# es_shield.net
KiCad netlist of a schematic drawn in EAGLE
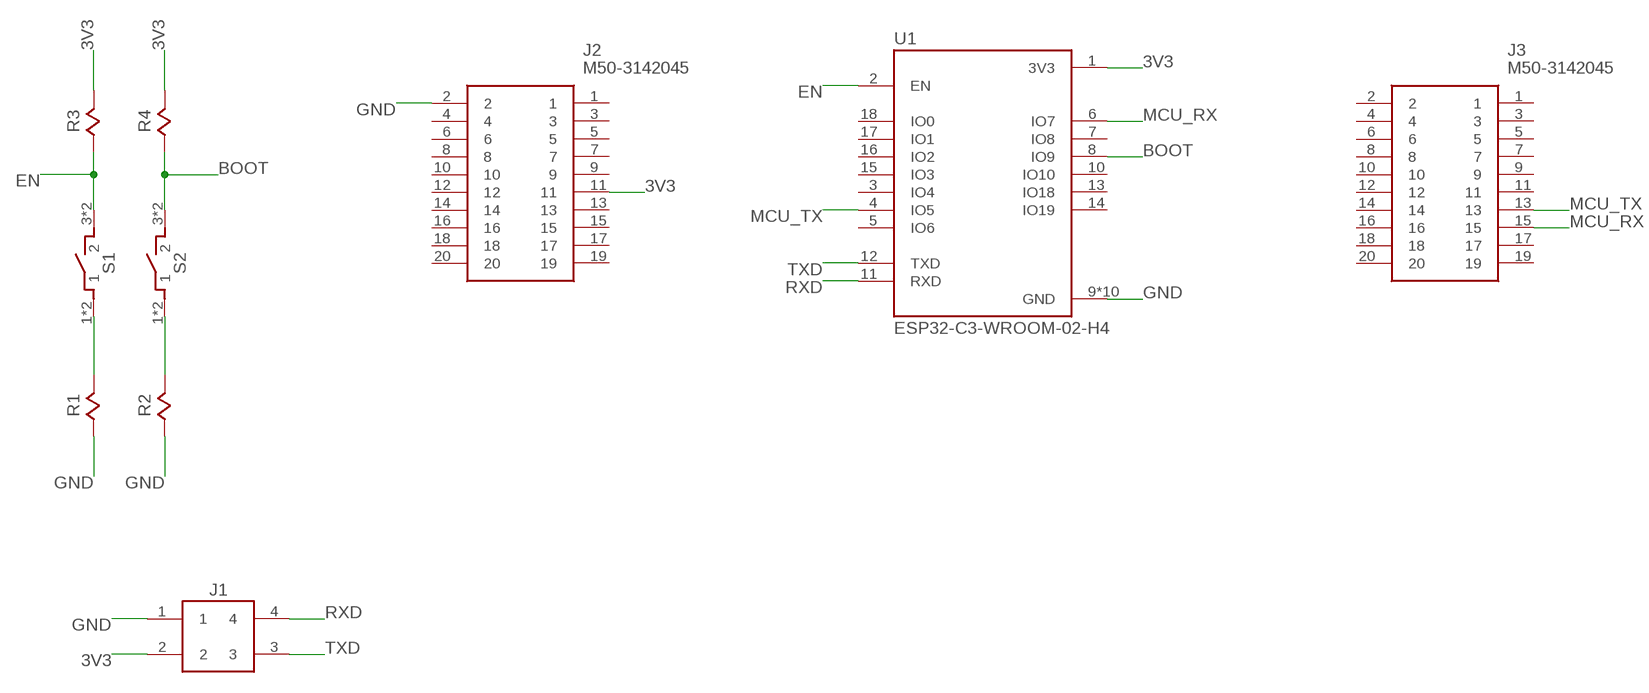
[diagram p0: schematic, sheet 1]

(export (version "E")
  (design (tool "Eeschema 10.0.6"))
  (components
    (comp (ref "J1")
      (value "MALE_HEADER_4X1")
      (footprint "eagle-import:4X1_HEADER")
      (libsource (lib "eagle-import") (part "MALE_HEADER_4X1"))
    )
    (comp (ref "J2")
      (value "M50-3142045")
      (footprint "eagle-import:M503142045")
      (fields (field (name "MOUSER_PART_NUMBER") "855-M50-3142045"))
      (libsource (lib "eagle-import") (part "M50-3142045"))
    )
    (comp (ref "J3")
      (value "M50-3142045")
      (footprint "eagle-import:M503142045")
      (fields (field (name "MOUSER_PART_NUMBER") "855-M50-3142045"))
      (libsource (lib "eagle-import") (part "M50-3142045"))
    )
    (comp (ref "R1")
      (value "RESISTOR")
      (footprint "eagle-import:0805")
      (libsource (lib "eagle-import") (part "RESISTOR"))
    )
    (comp (ref "R2")
      (value "RESISTOR")
      (footprint "eagle-import:0805")
      (libsource (lib "eagle-import") (part "RESISTOR"))
    )
    (comp (ref "R3")
      (value "RESISTOR")
      (footprint "eagle-import:0805")
      (libsource (lib "eagle-import") (part "RESISTOR"))
    )
    (comp (ref "R4")
      (value "RESISTOR")
      (footprint "eagle-import:0805")
      (libsource (lib "eagle-import") (part "RESISTOR"))
    )
    (comp (ref "S1")
      (value "TACTILE-SWITCH")
      (footprint "eagle-import:TACTILE-SWITCH")
      (libsource (lib "eagle-import") (part "TACTILE-SWITCH"))
    )
    (comp (ref "S2")
      (value "TACTILE-SWITCH")
      (footprint "eagle-import:TACTILE-SWITCH")
      (libsource (lib "eagle-import") (part "TACTILE-SWITCH"))
    )
    (comp (ref "U1")
      (value "ESP32-C3-WROOM-02-H4")
      (footprint "eagle-import:MODULE_ESP32-C3-WROOM-02-H4")
      (fields (field (name "MANUFACTURER") "Espressif"))
      (libsource (lib "eagle-import") (part "ESP32-C3-WROOM-02-H4"))
    )
  )
  (nets
    (net (code "1") (name "/3V3") (class "Default")
      (node (ref "J1") (pin "2") (pinfunction "2_2") (pintype "bidirectional"))
      (node (ref "J2") (pin "11") (pinfunction "11_11") (pintype "bidirectional"))
      (node (ref "R3") (pin "2") (pinfunction "2_2") (pintype "bidirectional"))
      (node (ref "R4") (pin "2") (pinfunction "2_2") (pintype "bidirectional"))
      (node (ref "U1") (pin "1") (pinfunction "3V3_1") (pintype "power_in"))
    )
    (net (code "2") (name "/BOOT") (class "Default")
      (node (ref "R4") (pin "1") (pinfunction "1_1") (pintype "bidirectional"))
      (node (ref "S2") (pin "3") (pinfunction "2_3") (pintype "bidirectional"))
      (node (ref "S2") (pin "4") (pinfunction "2_4") (pintype "bidirectional"))
      (node (ref "U1") (pin "8") (pinfunction "IO9_8") (pintype "bidirectional"))
    )
    (net (code "3") (name "/EN") (class "Default")
      (node (ref "R3") (pin "1") (pinfunction "1_1") (pintype "bidirectional"))
      (node (ref "S1") (pin "3") (pinfunction "2_3") (pintype "bidirectional"))
      (node (ref "S1") (pin "4") (pinfunction "2_4") (pintype "bidirectional"))
      (node (ref "U1") (pin "2") (pinfunction "EN_2") (pintype "input"))
    )
    (net (code "4") (name "/GND") (class "Default")
      (node (ref "J1") (pin "1") (pinfunction "1_1") (pintype "bidirectional"))
      (node (ref "J2") (pin "2") (pinfunction "2_2") (pintype "bidirectional"))
      (node (ref "R1") (pin "1") (pinfunction "1_1") (pintype "bidirectional"))
      (node (ref "R2") (pin "1") (pinfunction "1_1") (pintype "bidirectional"))
      (node (ref "U1") (pin "19") (pinfunction "GND_19") (pintype "power_in"))
      (node (ref "U1") (pin "20") (pinfunction "GND_20") (pintype "power_in"))
      (node (ref "U1") (pin "21") (pinfunction "GND_21") (pintype "power_in"))
      (node (ref "U1") (pin "22") (pinfunction "GND_22") (pintype "power_in"))
      (node (ref "U1") (pin "23") (pinfunction "GND_23") (pintype "power_in"))
      (node (ref "U1") (pin "24") (pinfunction "GND_24") (pintype "power_in"))
      (node (ref "U1") (pin "25") (pinfunction "GND_25") (pintype "power_in"))
      (node (ref "U1") (pin "26") (pinfunction "GND_26") (pintype "power_in"))
      (node (ref "U1") (pin "27") (pinfunction "GND_27") (pintype "power_in"))
      (node (ref "U1") (pin "9") (pinfunction "GND_9") (pintype "power_in"))
    )
    (net (code "5") (name "/MCU_RX") (class "Default")
      (node (ref "J3") (pin "15") (pinfunction "15_15") (pintype "bidirectional"))
      (node (ref "U1") (pin "6") (pinfunction "IO7_6") (pintype "bidirectional"))
    )
    (net (code "6") (name "/MCU_TX") (class "Default")
      (node (ref "J3") (pin "13") (pinfunction "13_13") (pintype "bidirectional"))
      (node (ref "U1") (pin "4") (pinfunction "IO5_4") (pintype "bidirectional"))
    )
    (net (code "7") (name "/RXD") (class "Default")
      (node (ref "J1") (pin "4") (pinfunction "4_4") (pintype "bidirectional"))
      (node (ref "U1") (pin "11") (pinfunction "RXD_11") (pintype "bidirectional"))
    )
    (net (code "8") (name "/TXD") (class "Default")
      (node (ref "J1") (pin "3") (pinfunction "3_3") (pintype "bidirectional"))
      (node (ref "U1") (pin "12") (pinfunction "TXD_12") (pintype "bidirectional"))
    )
    (net (code "9") (name "Net-(R1-Pad2)") (class "Default")
      (node (ref "R1") (pin "2") (pinfunction "2_2") (pintype "bidirectional"))
      (node (ref "S1") (pin "1") (pinfunction "1_1") (pintype "bidirectional"))
      (node (ref "S1") (pin "2") (pinfunction "1_2") (pintype "bidirectional"))
    )
    (net (code "10") (name "Net-(R2-Pad2)") (class "Default")
      (node (ref "R2") (pin "2") (pinfunction "2_2") (pintype "bidirectional"))
      (node (ref "S2") (pin "1") (pinfunction "1_1") (pintype "bidirectional"))
      (node (ref "S2") (pin "2") (pinfunction "1_2") (pintype "bidirectional"))
    )
    (net (code "11") (name "unconnected-(J2-Pad1)") (class "Default")
      (node (ref "J2") (pin "1") (pinfunction "1_1") (pintype "bidirectional"))
    )
    (net (code "12") (name "unconnected-(J2-Pad3)") (class "Default")
      (node (ref "J2") (pin "3") (pinfunction "3_3") (pintype "bidirectional"))
    )
    (net (code "13") (name "unconnected-(J2-Pad4)") (class "Default")
      (node (ref "J2") (pin "4") (pinfunction "4_4") (pintype "bidirectional"))
    )
    (net (code "14") (name "unconnected-(J2-Pad5)") (class "Default")
      (node (ref "J2") (pin "5") (pinfunction "5_5") (pintype "bidirectional"))
    )
    (net (code "15") (name "unconnected-(J2-Pad6)") (class "Default")
      (node (ref "J2") (pin "6") (pinfunction "6_6") (pintype "bidirectional"))
    )
    (net (code "16") (name "unconnected-(J2-Pad7)") (class "Default")
      (node (ref "J2") (pin "7") (pinfunction "7_7") (pintype "bidirectional"))
    )
    (net (code "17") (name "unconnected-(J2-Pad8)") (class "Default")
      (node (ref "J2") (pin "8") (pinfunction "8_8") (pintype "bidirectional"))
    )
    (net (code "18") (name "unconnected-(J2-Pad9)") (class "Default")
      (node (ref "J2") (pin "9") (pinfunction "9_9") (pintype "bidirectional"))
    )
    (net (code "19") (name "unconnected-(J2-Pad10)") (class "Default")
      (node (ref "J2") (pin "10") (pinfunction "10_10") (pintype "bidirectional"))
    )
    (net (code "20") (name "unconnected-(J2-Pad12)") (class "Default")
      (node (ref "J2") (pin "12") (pinfunction "12_12") (pintype "bidirectional"))
    )
    (net (code "21") (name "unconnected-(J2-Pad13)") (class "Default")
      (node (ref "J2") (pin "13") (pinfunction "13_13") (pintype "bidirectional"))
    )
    (net (code "22") (name "unconnected-(J2-Pad14)") (class "Default")
      (node (ref "J2") (pin "14") (pinfunction "14_14") (pintype "bidirectional"))
    )
    (net (code "23") (name "unconnected-(J2-Pad15)") (class "Default")
      (node (ref "J2") (pin "15") (pinfunction "15_15") (pintype "bidirectional"))
    )
    (net (code "24") (name "unconnected-(J2-Pad16)") (class "Default")
      (node (ref "J2") (pin "16") (pinfunction "16_16") (pintype "bidirectional"))
    )
    (net (code "25") (name "unconnected-(J2-Pad17)") (class "Default")
      (node (ref "J2") (pin "17") (pinfunction "17_17") (pintype "bidirectional"))
    )
    (net (code "26") (name "unconnected-(J2-Pad18)") (class "Default")
      (node (ref "J2") (pin "18") (pinfunction "18_18") (pintype "bidirectional"))
    )
    (net (code "27") (name "unconnected-(J2-Pad19)") (class "Default")
      (node (ref "J2") (pin "19") (pinfunction "19_19") (pintype "bidirectional"))
    )
    (net (code "28") (name "unconnected-(J2-Pad20)") (class "Default")
      (node (ref "J2") (pin "20") (pinfunction "20_20") (pintype "bidirectional"))
    )
    (net (code "29") (name "unconnected-(J3-Pad1)") (class "Default")
      (node (ref "J3") (pin "1") (pinfunction "1_1") (pintype "bidirectional"))
    )
    (net (code "30") (name "unconnected-(J3-Pad2)") (class "Default")
      (node (ref "J3") (pin "2") (pinfunction "2_2") (pintype "bidirectional"))
    )
    (net (code "31") (name "unconnected-(J3-Pad3)") (class "Default")
      (node (ref "J3") (pin "3") (pinfunction "3_3") (pintype "bidirectional"))
    )
    (net (code "32") (name "unconnected-(J3-Pad4)") (class "Default")
      (node (ref "J3") (pin "4") (pinfunction "4_4") (pintype "bidirectional"))
    )
    (net (code "33") (name "unconnected-(J3-Pad5)") (class "Default")
      (node (ref "J3") (pin "5") (pinfunction "5_5") (pintype "bidirectional"))
    )
    (net (code "34") (name "unconnected-(J3-Pad6)") (class "Default")
      (node (ref "J3") (pin "6") (pinfunction "6_6") (pintype "bidirectional"))
    )
    (net (code "35") (name "unconnected-(J3-Pad7)") (class "Default")
      (node (ref "J3") (pin "7") (pinfunction "7_7") (pintype "bidirectional"))
    )
    (net (code "36") (name "unconnected-(J3-Pad8)") (class "Default")
      (node (ref "J3") (pin "8") (pinfunction "8_8") (pintype "bidirectional"))
    )
    (net (code "37") (name "unconnected-(J3-Pad9)") (class "Default")
      (node (ref "J3") (pin "9") (pinfunction "9_9") (pintype "bidirectional"))
    )
    (net (code "38") (name "unconnected-(J3-Pad10)") (class "Default")
      (node (ref "J3") (pin "10") (pinfunction "10_10") (pintype "bidirectional"))
    )
    (net (code "39") (name "unconnected-(J3-Pad11)") (class "Default")
      (node (ref "J3") (pin "11") (pinfunction "11_11") (pintype "bidirectional"))
    )
    (net (code "40") (name "unconnected-(J3-Pad12)") (class "Default")
      (node (ref "J3") (pin "12") (pinfunction "12_12") (pintype "bidirectional"))
    )
    (net (code "41") (name "unconnected-(J3-Pad14)") (class "Default")
      (node (ref "J3") (pin "14") (pinfunction "14_14") (pintype "bidirectional"))
    )
    (net (code "42") (name "unconnected-(J3-Pad16)") (class "Default")
      (node (ref "J3") (pin "16") (pinfunction "16_16") (pintype "bidirectional"))
    )
    (net (code "43") (name "unconnected-(J3-Pad17)") (class "Default")
      (node (ref "J3") (pin "17") (pinfunction "17_17") (pintype "bidirectional"))
    )
    (net (code "44") (name "unconnected-(J3-Pad18)") (class "Default")
      (node (ref "J3") (pin "18") (pinfunction "18_18") (pintype "bidirectional"))
    )
    (net (code "45") (name "unconnected-(J3-Pad19)") (class "Default")
      (node (ref "J3") (pin "19") (pinfunction "19_19") (pintype "bidirectional"))
    )
    (net (code "46") (name "unconnected-(J3-Pad20)") (class "Default")
      (node (ref "J3") (pin "20") (pinfunction "20_20") (pintype "bidirectional"))
    )
    (net (code "47") (name "unconnected-(U1-IO0-Pad18)") (class "Default")
      (node (ref "U1") (pin "18") (pinfunction "IO0_18") (pintype "bidirectional"))
    )
    (net (code "48") (name "unconnected-(U1-IO1-Pad17)") (class "Default")
      (node (ref "U1") (pin "17") (pinfunction "IO1_17") (pintype "bidirectional"))
    )
    (net (code "49") (name "unconnected-(U1-IO2-Pad16)") (class "Default")
      (node (ref "U1") (pin "16") (pinfunction "IO2_16") (pintype "bidirectional"))
    )
    (net (code "50") (name "unconnected-(U1-IO3-Pad15)") (class "Default")
      (node (ref "U1") (pin "15") (pinfunction "IO3_15") (pintype "bidirectional"))
    )
    (net (code "51") (name "unconnected-(U1-IO4-Pad3)") (class "Default")
      (node (ref "U1") (pin "3") (pinfunction "IO4_3") (pintype "bidirectional"))
    )
    (net (code "52") (name "unconnected-(U1-IO6-Pad5)") (class "Default")
      (node (ref "U1") (pin "5") (pinfunction "IO6_5") (pintype "bidirectional"))
    )
    (net (code "53") (name "unconnected-(U1-IO8-Pad7)") (class "Default")
      (node (ref "U1") (pin "7") (pinfunction "IO8_7") (pintype "bidirectional"))
    )
    (net (code "54") (name "unconnected-(U1-IO10-Pad10)") (class "Default")
      (node (ref "U1") (pin "10") (pinfunction "IO10_10") (pintype "bidirectional"))
    )
    (net (code "55") (name "unconnected-(U1-IO18-Pad13)") (class "Default")
      (node (ref "U1") (pin "13") (pinfunction "IO18_13") (pintype "bidirectional"))
    )
    (net (code "56") (name "unconnected-(U1-IO19-Pad14)") (class "Default")
      (node (ref "U1") (pin "14") (pinfunction "IO19_14") (pintype "bidirectional"))
    )
  )
)
